# Shutdown_2019_v1_1_RTDS.net
KiCad netlist of a schematic drawn in Altium Designer
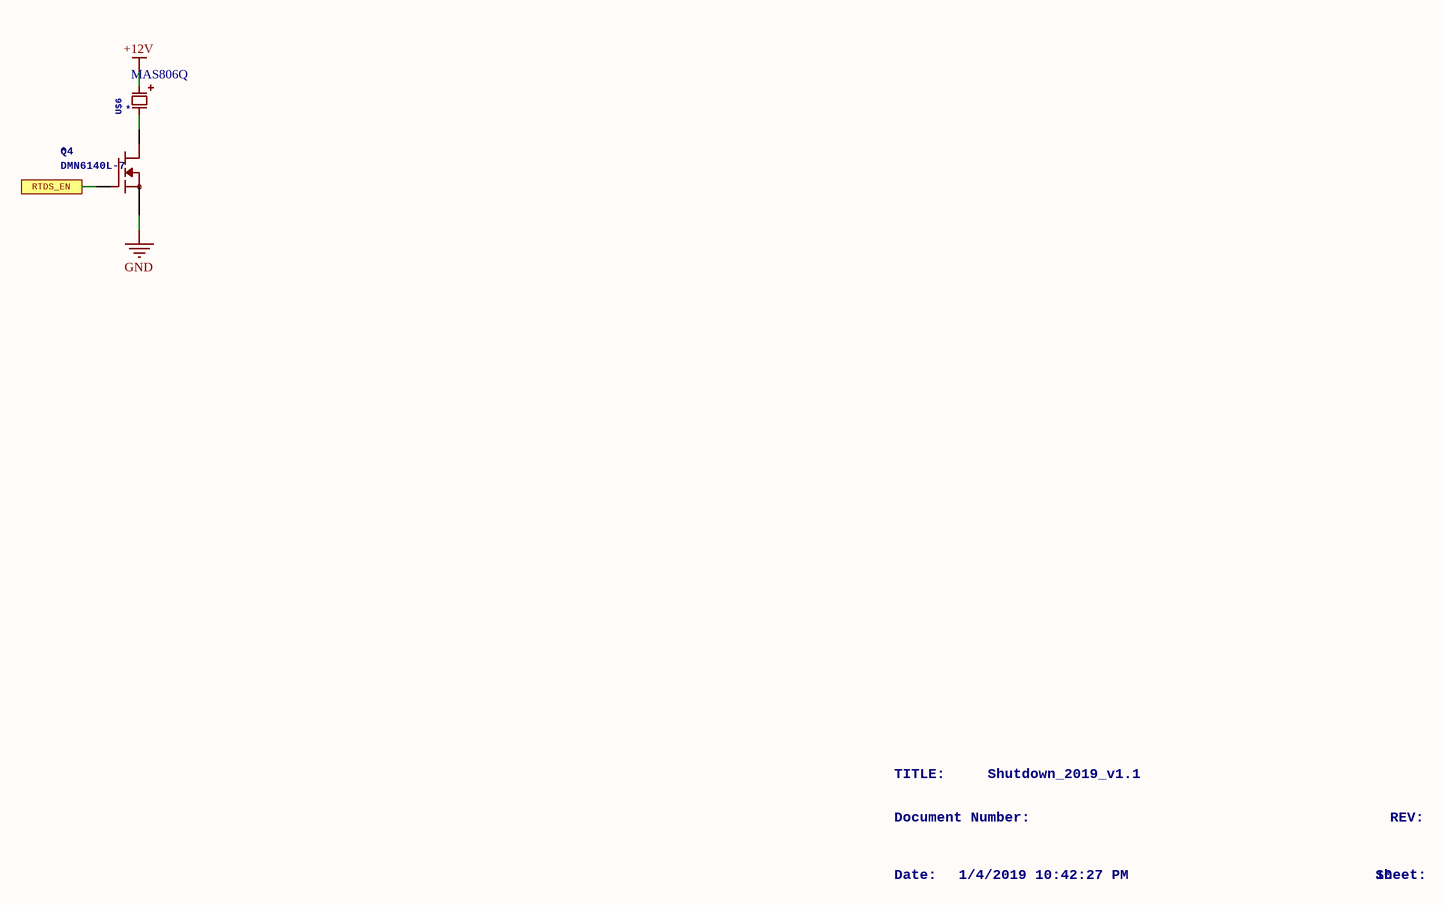
[diagram p0: Shutdown_2019_v1.1_RTDS.SchDoc]

(export (version "E")
  (design (tool "Eeschema 10.0.6"))
  (components
    (comp (ref "Q4")
      (value "DMN6140L-7")
      (footprint "SOT23")
      (description "DMN6140L-7 Vgs(th) = 3V, Rds(on) = 140mOhm, Vds(max) = 60V")
      (fields (field (name "NAME") "*"))
      (libsource (lib "TRANS") (part "DMN6140L-7"))
    )
    (comp (ref "U$6")
      (value "MAS806Q")
      (footprint "MAS806Q")
      (description "Mallory MAS806Q  PiezoElectric Buzzer  6-14V -- 103dB -- 50mA buzzerDatasheet")
      (fields (field (name "NAME") "*"))
      (libsource (lib "MALLORY") (part "MAS806Q"))
    )
  )
  (nets
    (net (code "1") (name "+12V") (class "Default")
      (node (ref "U$6") (pin "POS") (pinfunction "A_POS") (pintype "passive"))
    )
    (net (code "2") (name "/RTDS_EN") (class "Default")
      (node (ref "Q4") (pin "1") (pinfunction "G_1") (pintype "passive"))
    )
    (net (code "3") (name "GND") (class "Default")
      (node (ref "Q4") (pin "2") (pinfunction "S_2") (pintype "passive"))
    )
    (net (code "4") (name "Net-(Q4-D)") (class "Default")
      (node (ref "Q4") (pin "3") (pinfunction "D_3") (pintype "passive"))
      (node (ref "U$6") (pin "NEG") (pinfunction "B_NEG") (pintype "output"))
    )
  )
)
